# Dot.net
KiCad netlist of a schematic drawn in EAGLE
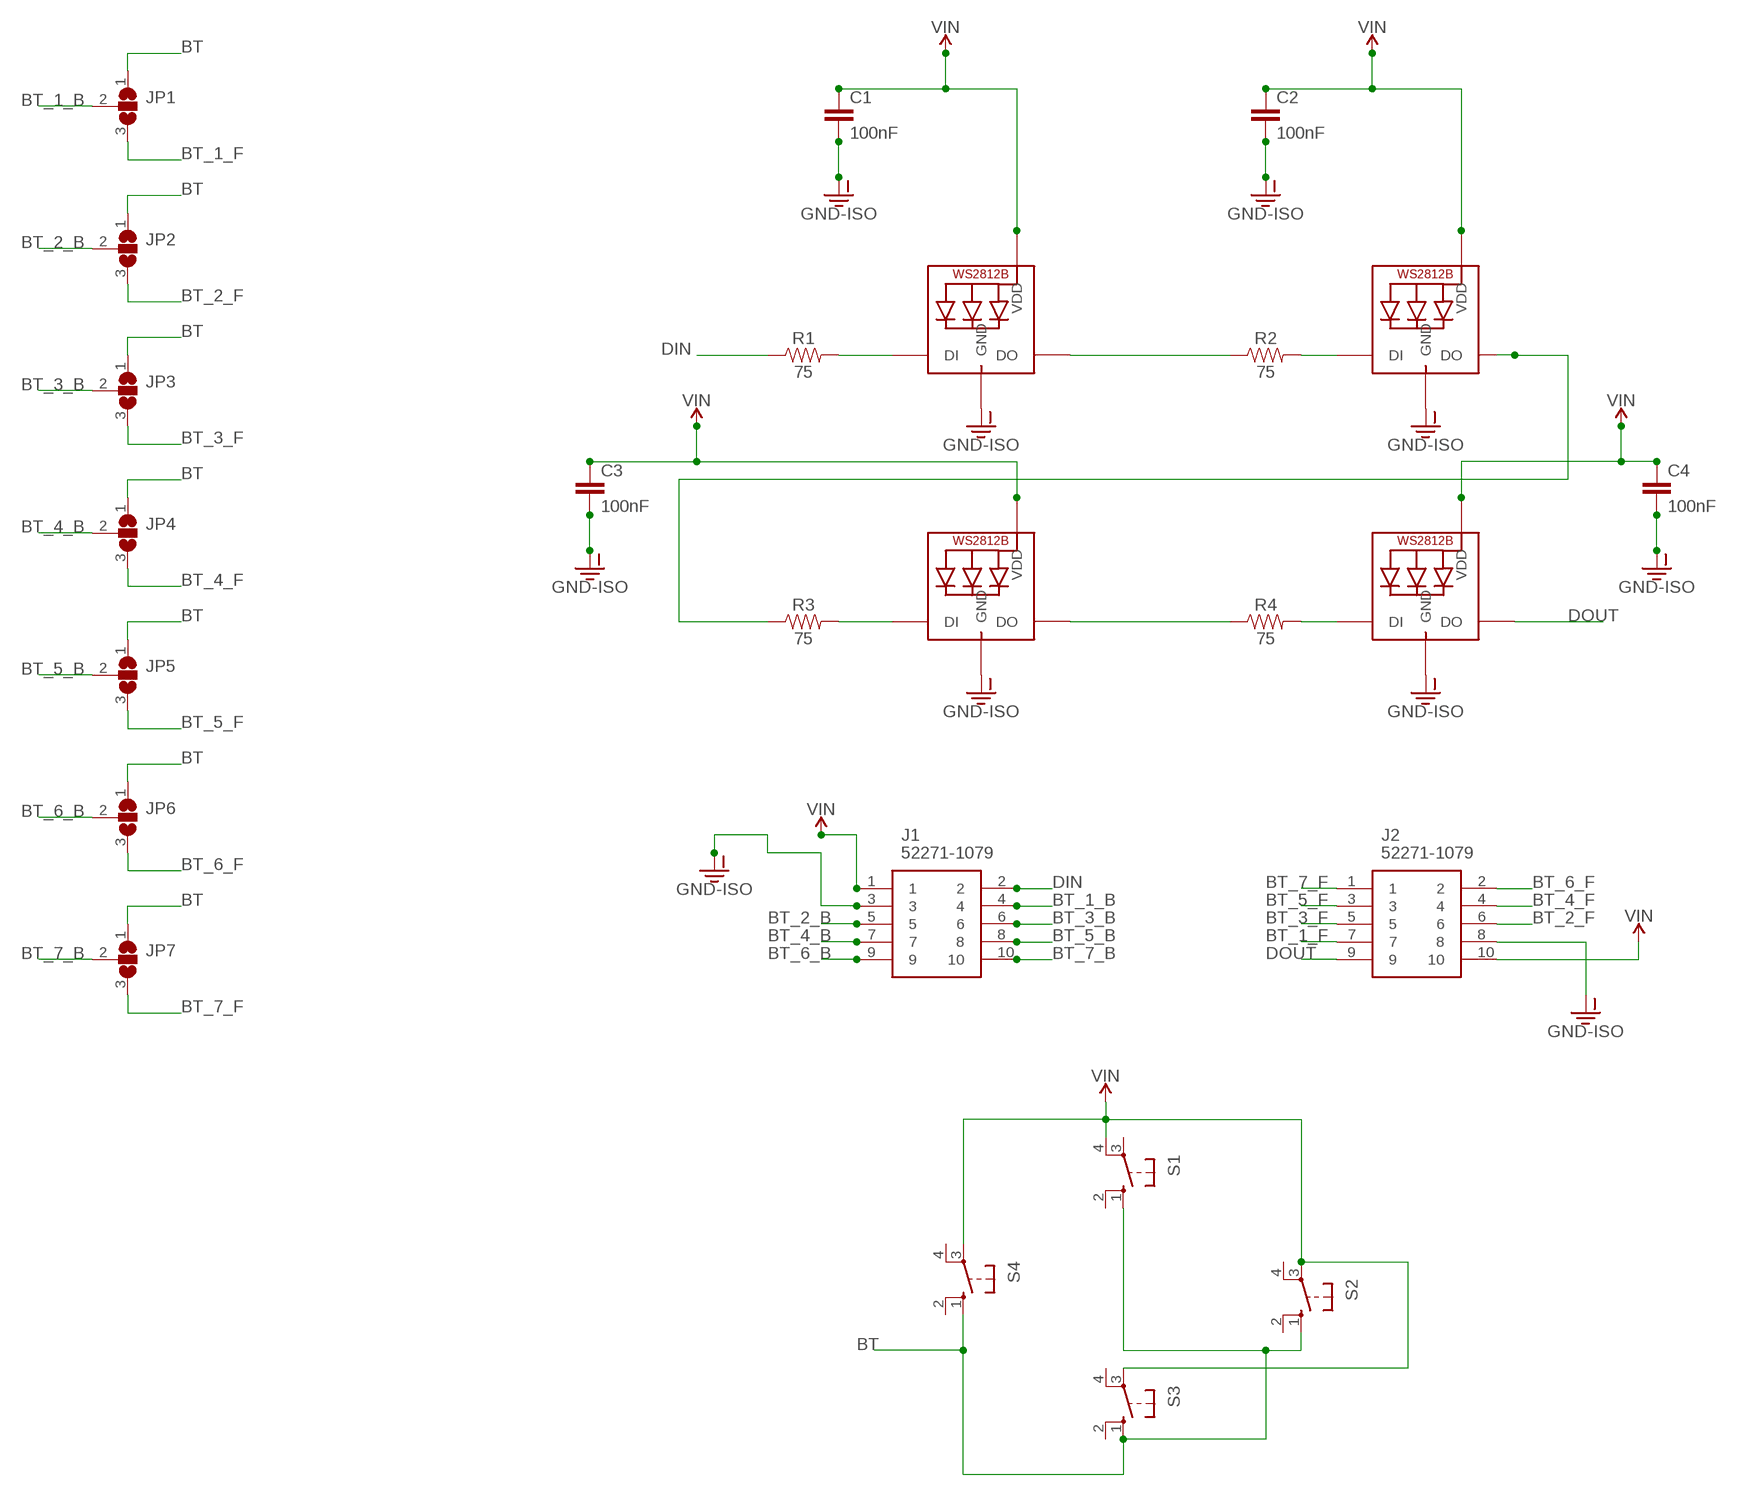
[diagram p0: schematic, sheet 1]

(export (version "E")
  (design (tool "Eeschema 10.0.6"))
  (components
    (comp (ref "C1")
      (value "100nF")
      (footprint "eagle-import:0603")
      (libsource (lib "eagle-import") (part "100PF-0603-50V-5%"))
    )
    (comp (ref "C2")
      (value "100nF")
      (footprint "eagle-import:0603")
      (libsource (lib "eagle-import") (part "100PF-0603-50V-5%"))
    )
    (comp (ref "C3")
      (value "100nF")
      (footprint "eagle-import:0603")
      (libsource (lib "eagle-import") (part "100PF-0603-50V-5%"))
    )
    (comp (ref "C4")
      (value "100nF")
      (footprint "eagle-import:0603")
      (libsource (lib "eagle-import") (part "100PF-0603-50V-5%"))
    )
    (comp (ref "J1")
      (value "52271-1079")
      (footprint "eagle-import:52271-1079")
      (fields (field (name "RS_PART_NUMBER") "5144329P"))
      (libsource (lib "eagle-import") (part "52271-1079"))
    )
    (comp (ref "J2")
      (value "52271-1079")
      (footprint "eagle-import:52271-1079")
      (fields (field (name "RS_PART_NUMBER") "5144329P"))
      (libsource (lib "eagle-import") (part "52271-1079"))
    )
    (comp (ref "JP1")
      (value "SJ2W")
      (footprint "eagle-import:SJ_2")
      (libsource (lib "eagle-import") (part "SJ2W"))
    )
    (comp (ref "JP2")
      (value "SJ2W")
      (footprint "eagle-import:SJ_2")
      (libsource (lib "eagle-import") (part "SJ2W"))
    )
    (comp (ref "JP3")
      (value "SJ2W")
      (footprint "eagle-import:SJ_2")
      (libsource (lib "eagle-import") (part "SJ2W"))
    )
    (comp (ref "JP4")
      (value "SJ2W")
      (footprint "eagle-import:SJ_2")
      (libsource (lib "eagle-import") (part "SJ2W"))
    )
    (comp (ref "JP5")
      (value "SJ2W")
      (footprint "eagle-import:SJ_2")
      (libsource (lib "eagle-import") (part "SJ2W"))
    )
    (comp (ref "JP6")
      (value "SJ2W")
      (footprint "eagle-import:SJ_2")
      (libsource (lib "eagle-import") (part "SJ2W"))
    )
    (comp (ref "JP7")
      (value "SJ2W")
      (footprint "eagle-import:SJ_2")
      (libsource (lib "eagle-import") (part "SJ2W"))
    )
    (comp (ref "LED1")
      (value "WS2812B5050")
      (footprint "eagle-import:WS2812B")
      (libsource (lib "eagle-import") (part "WS2812B5050"))
    )
    (comp (ref "LED2")
      (value "WS2812B5050")
      (footprint "eagle-import:WS2812B")
      (libsource (lib "eagle-import") (part "WS2812B5050"))
    )
    (comp (ref "LED3")
      (value "WS2812B5050")
      (footprint "eagle-import:WS2812B")
      (libsource (lib "eagle-import") (part "WS2812B5050"))
    )
    (comp (ref "LED4")
      (value "WS2812B5050")
      (footprint "eagle-import:WS2812B")
      (libsource (lib "eagle-import") (part "WS2812B5050"))
    )
    (comp (ref "R1")
      (value "75")
      (footprint "eagle-import:0603")
      (libsource (lib "eagle-import") (part "75KOHM-0603-1/10W-1%"))
    )
    (comp (ref "R2")
      (value "75")
      (footprint "eagle-import:0603")
      (libsource (lib "eagle-import") (part "75KOHM-0603-1/10W-1%"))
    )
    (comp (ref "R3")
      (value "75")
      (footprint "eagle-import:0603")
      (libsource (lib "eagle-import") (part "75KOHM-0603-1/10W-1%"))
    )
    (comp (ref "R4")
      (value "75")
      (footprint "eagle-import:0603")
      (libsource (lib "eagle-import") (part "75KOHM-0603-1/10W-1%"))
    )
    (comp (ref "S1")
      (value "10-XX")
      (footprint "eagle-import:B3F-10XX")
      (fields (field (name "MPN") "B3F-1000"))
      (libsource (lib "eagle-import") (part "10-XX"))
    )
    (comp (ref "S2")
      (value "10-XX")
      (footprint "eagle-import:B3F-10XX")
      (fields (field (name "MPN") "B3F-1000"))
      (libsource (lib "eagle-import") (part "10-XX"))
    )
    (comp (ref "S3")
      (value "10-XX")
      (footprint "eagle-import:B3F-10XX")
      (fields (field (name "MPN") "B3F-1000"))
      (libsource (lib "eagle-import") (part "10-XX"))
    )
    (comp (ref "S4")
      (value "10-XX")
      (footprint "eagle-import:B3F-10XX")
      (fields (field (name "MPN") "B3F-1000"))
      (libsource (lib "eagle-import") (part "10-XX"))
    )
  )
  (nets
    (net (code "1") (name "/BT") (class "Default")
      (node (ref "JP1") (pin "1") (pinfunction "1_1") (pintype "passive"))
      (node (ref "JP2") (pin "1") (pinfunction "1_1") (pintype "passive"))
      (node (ref "JP3") (pin "1") (pinfunction "1_1") (pintype "passive"))
      (node (ref "JP4") (pin "1") (pinfunction "1_1") (pintype "passive"))
      (node (ref "JP5") (pin "1") (pinfunction "1_1") (pintype "passive"))
      (node (ref "JP6") (pin "1") (pinfunction "1_1") (pintype "passive"))
      (node (ref "JP7") (pin "1") (pinfunction "1_1") (pintype "passive"))
      (node (ref "S1") (pin "1") (pinfunction "S_1") (pintype "passive"))
      (node (ref "S2") (pin "1") (pinfunction "S_1") (pintype "passive"))
      (node (ref "S3") (pin "1") (pinfunction "S_1") (pintype "passive"))
      (node (ref "S4") (pin "1") (pinfunction "S_1") (pintype "passive"))
    )
    (net (code "2") (name "/BT_1_B") (class "Default")
      (node (ref "J1") (pin "4") (pinfunction "4_4") (pintype "bidirectional"))
      (node (ref "JP1") (pin "2") (pinfunction "2_2") (pintype "passive"))
    )
    (net (code "3") (name "/BT_1_F") (class "Default")
      (node (ref "J2") (pin "7") (pinfunction "7_7") (pintype "bidirectional"))
      (node (ref "JP1") (pin "3") (pinfunction "3_3") (pintype "passive"))
    )
    (net (code "4") (name "/BT_2_B") (class "Default")
      (node (ref "J1") (pin "5") (pinfunction "5_5") (pintype "bidirectional"))
      (node (ref "JP2") (pin "2") (pinfunction "2_2") (pintype "passive"))
    )
    (net (code "5") (name "/BT_2_F") (class "Default")
      (node (ref "J2") (pin "6") (pinfunction "6_6") (pintype "bidirectional"))
      (node (ref "JP2") (pin "3") (pinfunction "3_3") (pintype "passive"))
    )
    (net (code "6") (name "/BT_3_B") (class "Default")
      (node (ref "J1") (pin "6") (pinfunction "6_6") (pintype "bidirectional"))
      (node (ref "JP3") (pin "2") (pinfunction "2_2") (pintype "passive"))
    )
    (net (code "7") (name "/BT_3_F") (class "Default")
      (node (ref "J2") (pin "5") (pinfunction "5_5") (pintype "bidirectional"))
      (node (ref "JP3") (pin "3") (pinfunction "3_3") (pintype "passive"))
    )
    (net (code "8") (name "/BT_4_B") (class "Default")
      (node (ref "J1") (pin "7") (pinfunction "7_7") (pintype "bidirectional"))
      (node (ref "JP4") (pin "2") (pinfunction "2_2") (pintype "passive"))
    )
    (net (code "9") (name "/BT_4_F") (class "Default")
      (node (ref "J2") (pin "4") (pinfunction "4_4") (pintype "bidirectional"))
      (node (ref "JP4") (pin "3") (pinfunction "3_3") (pintype "passive"))
    )
    (net (code "10") (name "/BT_5_B") (class "Default")
      (node (ref "J1") (pin "8") (pinfunction "8_8") (pintype "bidirectional"))
      (node (ref "JP5") (pin "2") (pinfunction "2_2") (pintype "passive"))
    )
    (net (code "11") (name "/BT_5_F") (class "Default")
      (node (ref "J2") (pin "3") (pinfunction "3_3") (pintype "bidirectional"))
      (node (ref "JP5") (pin "3") (pinfunction "3_3") (pintype "passive"))
    )
    (net (code "12") (name "/BT_6_B") (class "Default")
      (node (ref "J1") (pin "9") (pinfunction "9_9") (pintype "bidirectional"))
      (node (ref "JP6") (pin "2") (pinfunction "2_2") (pintype "passive"))
    )
    (net (code "13") (name "/BT_6_F") (class "Default")
      (node (ref "J2") (pin "2") (pinfunction "2_2") (pintype "bidirectional"))
      (node (ref "JP6") (pin "3") (pinfunction "3_3") (pintype "passive"))
    )
    (net (code "14") (name "/BT_7_B") (class "Default")
      (node (ref "J1") (pin "10") (pinfunction "10_10") (pintype "bidirectional"))
      (node (ref "JP7") (pin "2") (pinfunction "2_2") (pintype "passive"))
    )
    (net (code "15") (name "/BT_7_F") (class "Default")
      (node (ref "J2") (pin "1") (pinfunction "1_1") (pintype "bidirectional"))
      (node (ref "JP7") (pin "3") (pinfunction "3_3") (pintype "passive"))
    )
    (net (code "16") (name "/DIN") (class "Default")
      (node (ref "J1") (pin "2") (pinfunction "2_2") (pintype "bidirectional"))
      (node (ref "R1") (pin "1") (pinfunction "1_1") (pintype "passive"))
    )
    (net (code "17") (name "/DOUT") (class "Default")
      (node (ref "J2") (pin "9") (pinfunction "9_9") (pintype "bidirectional"))
      (node (ref "LED4") (pin "2-DOUT") (pinfunction "DO_2-DOUT") (pintype "output"))
    )
    (net (code "18") (name "GND-ISO") (class "Default")
      (node (ref "C1") (pin "2") (pinfunction "2_2") (pintype "passive"))
      (node (ref "C2") (pin "2") (pinfunction "2_2") (pintype "passive"))
      (node (ref "C3") (pin "2") (pinfunction "2_2") (pintype "passive"))
      (node (ref "C4") (pin "2") (pinfunction "2_2") (pintype "passive"))
      (node (ref "J1") (pin "3") (pinfunction "3_3") (pintype "bidirectional"))
      (node (ref "J2") (pin "8") (pinfunction "8_8") (pintype "bidirectional"))
      (node (ref "LED1") (pin "3-GND") (pinfunction "GND_3-GND") (pintype "power_in"))
      (node (ref "LED2") (pin "3-GND") (pinfunction "GND_3-GND") (pintype "power_in"))
      (node (ref "LED3") (pin "3-GND") (pinfunction "GND_3-GND") (pintype "power_in"))
      (node (ref "LED4") (pin "3-GND") (pinfunction "GND_3-GND") (pintype "power_in"))
    )
    (net (code "19") (name "Net-(LED1-DI)") (class "Default")
      (node (ref "LED1") (pin "4-DIN") (pinfunction "DI_4-DIN") (pintype "input"))
      (node (ref "R1") (pin "2") (pinfunction "2_2") (pintype "passive"))
    )
    (net (code "20") (name "Net-(LED1-DO)") (class "Default")
      (node (ref "LED1") (pin "2-DOUT") (pinfunction "DO_2-DOUT") (pintype "output"))
      (node (ref "R2") (pin "1") (pinfunction "1_1") (pintype "passive"))
    )
    (net (code "21") (name "Net-(LED2-DI)") (class "Default")
      (node (ref "LED2") (pin "4-DIN") (pinfunction "DI_4-DIN") (pintype "input"))
      (node (ref "R2") (pin "2") (pinfunction "2_2") (pintype "passive"))
    )
    (net (code "22") (name "Net-(LED2-DO)") (class "Default")
      (node (ref "LED2") (pin "2-DOUT") (pinfunction "DO_2-DOUT") (pintype "output"))
      (node (ref "R3") (pin "1") (pinfunction "1_1") (pintype "passive"))
    )
    (net (code "23") (name "Net-(LED3-DI)") (class "Default")
      (node (ref "LED3") (pin "4-DIN") (pinfunction "DI_4-DIN") (pintype "input"))
      (node (ref "R3") (pin "2") (pinfunction "2_2") (pintype "passive"))
    )
    (net (code "24") (name "Net-(LED3-DO)") (class "Default")
      (node (ref "LED3") (pin "2-DOUT") (pinfunction "DO_2-DOUT") (pintype "output"))
      (node (ref "R4") (pin "1") (pinfunction "1_1") (pintype "passive"))
    )
    (net (code "25") (name "Net-(LED4-DI)") (class "Default")
      (node (ref "LED4") (pin "4-DIN") (pinfunction "DI_4-DIN") (pintype "input"))
      (node (ref "R4") (pin "2") (pinfunction "2_2") (pintype "passive"))
    )
    (net (code "26") (name "VIN") (class "Default")
      (node (ref "C1") (pin "1") (pinfunction "1_1") (pintype "passive"))
      (node (ref "C2") (pin "1") (pinfunction "1_1") (pintype "passive"))
      (node (ref "C3") (pin "1") (pinfunction "1_1") (pintype "passive"))
      (node (ref "C4") (pin "1") (pinfunction "1_1") (pintype "passive"))
      (node (ref "J1") (pin "1") (pinfunction "1_1") (pintype "bidirectional"))
      (node (ref "J2") (pin "10") (pinfunction "10_10") (pintype "bidirectional"))
      (node (ref "LED1") (pin "1-VDD") (pinfunction "VDD_1-VDD") (pintype "power_in"))
      (node (ref "LED2") (pin "1-VDD") (pinfunction "VDD_1-VDD") (pintype "power_in"))
      (node (ref "LED3") (pin "1-VDD") (pinfunction "VDD_1-VDD") (pintype "power_in"))
      (node (ref "LED4") (pin "1-VDD") (pinfunction "VDD_1-VDD") (pintype "power_in"))
      (node (ref "S1") (pin "4") (pinfunction "P1_4") (pintype "passive"))
      (node (ref "S2") (pin "3") (pinfunction "P_3") (pintype "passive"))
      (node (ref "S3") (pin "3") (pinfunction "P_3") (pintype "passive"))
      (node (ref "S4") (pin "3") (pinfunction "P_3") (pintype "passive"))
    )
    (net (code "27") (name "unconnected-(S1-P-Pad3)") (class "Default")
      (node (ref "S1") (pin "3") (pinfunction "P_3") (pintype "passive"))
    )
    (net (code "28") (name "unconnected-(S1-S1-Pad2)") (class "Default")
      (node (ref "S1") (pin "2") (pinfunction "S1_2") (pintype "passive"))
    )
    (net (code "29") (name "unconnected-(S2-P1-Pad4)") (class "Default")
      (node (ref "S2") (pin "4") (pinfunction "P1_4") (pintype "passive"))
    )
    (net (code "30") (name "unconnected-(S2-S1-Pad2)") (class "Default")
      (node (ref "S2") (pin "2") (pinfunction "S1_2") (pintype "passive"))
    )
    (net (code "31") (name "unconnected-(S3-P1-Pad4)") (class "Default")
      (node (ref "S3") (pin "4") (pinfunction "P1_4") (pintype "passive"))
    )
    (net (code "32") (name "unconnected-(S3-S1-Pad2)") (class "Default")
      (node (ref "S3") (pin "2") (pinfunction "S1_2") (pintype "passive"))
    )
    (net (code "33") (name "unconnected-(S4-P1-Pad4)") (class "Default")
      (node (ref "S4") (pin "4") (pinfunction "P1_4") (pintype "passive"))
    )
    (net (code "34") (name "unconnected-(S4-S1-Pad2)") (class "Default")
      (node (ref "S4") (pin "2") (pinfunction "S1_2") (pintype "passive"))
    )
  )
)
